# can.net
KiCad netlist of a schematic drawn in Altium Designer
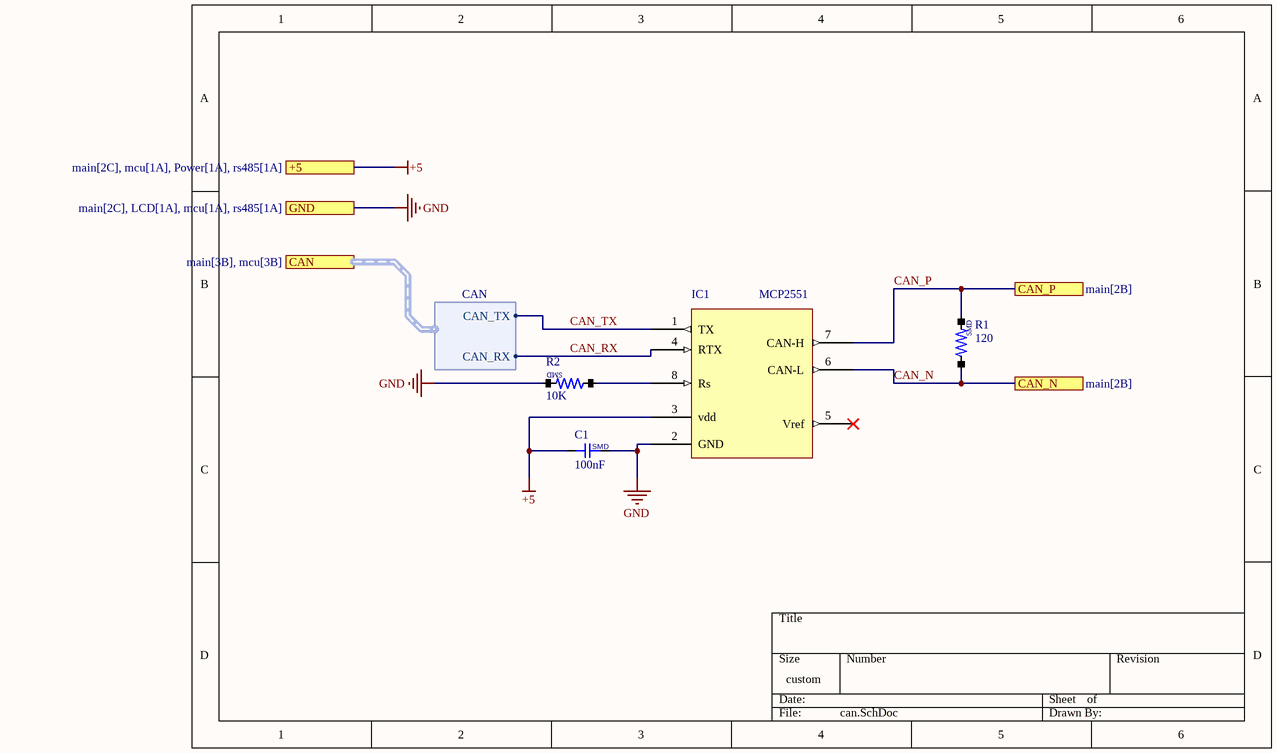
[diagram p0: can.SchDoc]

(export (version "E")
  (design (tool "Eeschema 10.0.6"))
  (components
    (comp (ref "C1") (value "100nF") (footprint "CAP-0603") (libsource (lib "kave-eng-pro") (part "cap_smd")))
    (comp (ref "IC1") (value "MCP2551") (footprint "SOP-8") (libsource (lib "kave-eng-pro") (part "MCP2551")))
    (comp (ref "R1") (value "120") (footprint "RES/1206") (libsource (lib "kave-eng-pro") (part "RES/SMD")))
    (comp (ref "R2") (value "10K") (footprint "RES/0603") (libsource (lib "") (part "RES/SMD_1")))
  )
  (nets
    (net (code "2") (name "+5") (class "Default")
      (node (ref "C1") (pin "1") (pintype "passive"))
      (node (ref "IC1") (pin "3") (pinfunction "vdd_3") (pintype "power_in"))
    )
    (net (code "3") (name "/CAN_N") (class "Default")
      (node (ref "IC1") (pin "6") (pinfunction "CAN-L_6") (pintype "output"))
      (node (ref "R1") (pin "1") (pinfunction "1_1") (pintype "passive"))
    )
    (net (code "4") (name "/CAN_P") (class "Default")
      (node (ref "IC1") (pin "7") (pinfunction "CAN-H_7") (pintype "output"))
      (node (ref "R1") (pin "2") (pinfunction "2_2") (pintype "passive"))
    )
    (net (code "5") (name "/CAN_RX") (class "Default")
      (node (ref "IC1") (pin "4") (pinfunction "RTX_4") (pintype "input"))
    )
    (net (code "6") (name "/CAN_TX") (class "Default")
      (node (ref "IC1") (pin "1") (pinfunction "TX_1") (pintype "output"))
    )
    (net (code "8") (name "GND") (class "Default")
      (node (ref "C1") (pin "2") (pintype "passive"))
      (node (ref "IC1") (pin "2") (pinfunction "GND_2") (pintype "power_in"))
      (node (ref "R2") (pin "2") (pinfunction "2_2") (pintype "passive"))
    )
    (net (code "9") (name "Net-(IC1-Rs)") (class "Default")
      (node (ref "IC1") (pin "8") (pinfunction "Rs_8") (pintype "input"))
      (node (ref "R2") (pin "1") (pinfunction "1_1") (pintype "passive"))
    )
    (net (code "10") (name "unconnected-(IC1-Vref-Pad5)") (class "Default")
      (node (ref "IC1") (pin "5") (pinfunction "Vref_5") (pintype "output+no_connect"))
    )
  )
)
